# sense_part.net
KiCad netlist of a schematic drawn in EAGLE
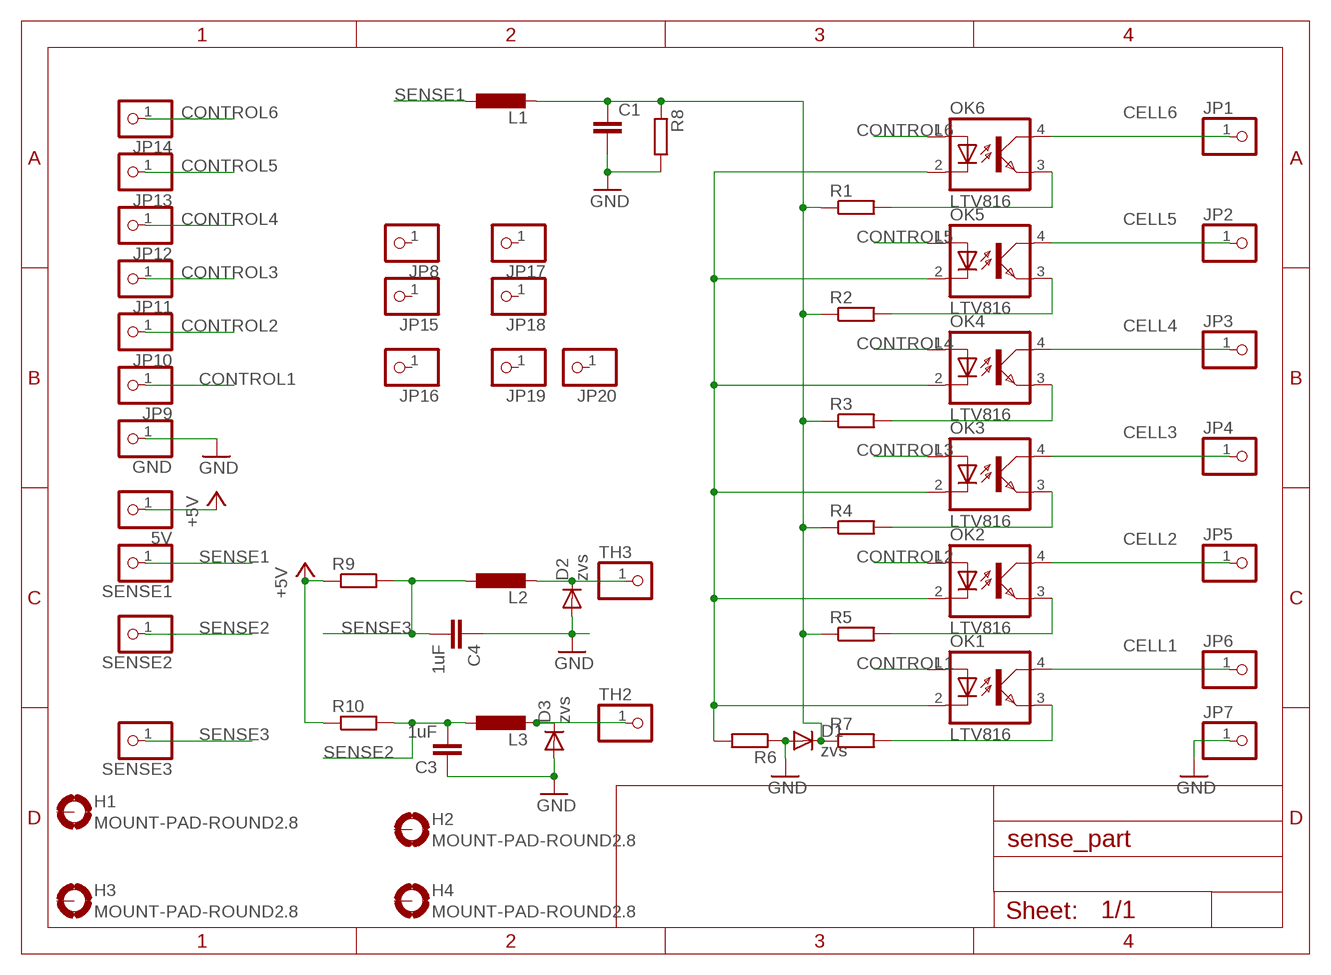
[diagram p0: schematic, sheet 1]

(export (version "E")
  (design (tool "Eeschema 10.0.6"))
  (components
    (comp (ref "5V")
      (value "PINHD-1X1")
      (footprint "eagle-import:1X01")
      (libsource (lib "eagle-import") (part "PINHD-1X1"))
    )
    (comp (ref "C1")
      (value "C-EU050-030X075")
      (footprint "eagle-import:C050-030X075")
      (libsource (lib "eagle-import") (part "C-EU050-030X075"))
    )
    (comp (ref "C3")
      (value "1uF")
      (footprint "eagle-import:C025-024X044")
      (libsource (lib "eagle-import") (part "resistor_C-EU025-024X044"))
    )
    (comp (ref "C4")
      (value "1uF")
      (footprint "eagle-import:C025-024X044")
      (libsource (lib "eagle-import") (part "resistor_C-EU025-024X044"))
    )
    (comp (ref "D1")
      (value "zvs")
      (footprint "eagle-import:SOD-123_MINI-SMA")
      (libsource (lib "eagle-import") (part "CGRM400-G1"))
    )
    (comp (ref "D2")
      (value "zvs")
      (footprint "eagle-import:SOD-123_MINI-SMA")
      (libsource (lib "eagle-import") (part "CGRM400-G1"))
    )
    (comp (ref "D3")
      (value "zvs")
      (footprint "eagle-import:SOD-123_MINI-SMA")
      (libsource (lib "eagle-import") (part "CGRM400-G1"))
    )
    (comp (ref "GND")
      (value "PINHD-1X1")
      (footprint "eagle-import:1X01")
      (libsource (lib "eagle-import") (part "PINHD-1X1"))
    )
    (comp (ref "H1")
      (value "MOUNT-PAD-ROUND2.8")
      (footprint "eagle-import:2,8-PAD")
      (libsource (lib "eagle-import") (part "MOUNT-PAD-ROUND2.8"))
    )
    (comp (ref "H2")
      (value "MOUNT-PAD-ROUND2.8")
      (footprint "eagle-import:2,8-PAD")
      (libsource (lib "eagle-import") (part "MOUNT-PAD-ROUND2.8"))
    )
    (comp (ref "H3")
      (value "MOUNT-PAD-ROUND2.8")
      (footprint "eagle-import:2,8-PAD")
      (libsource (lib "eagle-import") (part "MOUNT-PAD-ROUND2.8"))
    )
    (comp (ref "H4")
      (value "MOUNT-PAD-ROUND2.8")
      (footprint "eagle-import:2,8-PAD")
      (libsource (lib "eagle-import") (part "MOUNT-PAD-ROUND2.8"))
    )
    (comp (ref "JP1")
      (value "PINHD-1X1")
      (footprint "eagle-import:1X01")
      (libsource (lib "eagle-import") (part "PINHD-1X1"))
    )
    (comp (ref "JP2")
      (value "PINHD-1X1")
      (footprint "eagle-import:1X01")
      (libsource (lib "eagle-import") (part "PINHD-1X1"))
    )
    (comp (ref "JP3")
      (value "PINHD-1X1")
      (footprint "eagle-import:1X01")
      (libsource (lib "eagle-import") (part "PINHD-1X1"))
    )
    (comp (ref "JP4")
      (value "PINHD-1X1")
      (footprint "eagle-import:1X01")
      (libsource (lib "eagle-import") (part "PINHD-1X1"))
    )
    (comp (ref "JP5")
      (value "PINHD-1X1")
      (footprint "eagle-import:1X01")
      (libsource (lib "eagle-import") (part "PINHD-1X1"))
    )
    (comp (ref "JP6")
      (value "PINHD-1X1")
      (footprint "eagle-import:1X01")
      (libsource (lib "eagle-import") (part "PINHD-1X1"))
    )
    (comp (ref "JP7")
      (value "PINHD-1X1")
      (footprint "eagle-import:1X01")
      (libsource (lib "eagle-import") (part "PINHD-1X1"))
    )
    (comp (ref "JP8")
      (value "PINHD-1X1")
      (footprint "eagle-import:1X01")
      (libsource (lib "eagle-import") (part "PINHD-1X1"))
    )
    (comp (ref "JP9")
      (value "PINHD-1X1")
      (footprint "eagle-import:1X01")
      (libsource (lib "eagle-import") (part "PINHD-1X1"))
    )
    (comp (ref "JP10")
      (value "PINHD-1X1")
      (footprint "eagle-import:1X01")
      (libsource (lib "eagle-import") (part "PINHD-1X1"))
    )
    (comp (ref "JP11")
      (value "PINHD-1X1")
      (footprint "eagle-import:1X01")
      (libsource (lib "eagle-import") (part "PINHD-1X1"))
    )
    (comp (ref "JP12")
      (value "PINHD-1X1")
      (footprint "eagle-import:1X01")
      (libsource (lib "eagle-import") (part "PINHD-1X1"))
    )
    (comp (ref "JP13")
      (value "PINHD-1X1")
      (footprint "eagle-import:1X01")
      (libsource (lib "eagle-import") (part "PINHD-1X1"))
    )
    (comp (ref "JP14")
      (value "PINHD-1X1")
      (footprint "eagle-import:1X01")
      (libsource (lib "eagle-import") (part "PINHD-1X1"))
    )
    (comp (ref "JP15")
      (value "PINHD-1X1")
      (footprint "eagle-import:1X01")
      (libsource (lib "eagle-import") (part "PINHD-1X1"))
    )
    (comp (ref "JP16")
      (value "PINHD-1X1")
      (footprint "eagle-import:1X01")
      (libsource (lib "eagle-import") (part "PINHD-1X1"))
    )
    (comp (ref "JP17")
      (value "PINHD-1X1")
      (footprint "eagle-import:1X01")
      (libsource (lib "eagle-import") (part "PINHD-1X1"))
    )
    (comp (ref "JP18")
      (value "PINHD-1X1")
      (footprint "eagle-import:1X01")
      (libsource (lib "eagle-import") (part "PINHD-1X1"))
    )
    (comp (ref "JP19")
      (value "PINHD-1X1")
      (footprint "eagle-import:1X01")
      (libsource (lib "eagle-import") (part "PINHD-1X1"))
    )
    (comp (ref "JP20")
      (value "PINHD-1X1")
      (footprint "eagle-import:1X01")
      (libsource (lib "eagle-import") (part "PINHD-1X1"))
    )
    (comp (ref "L1")
      (value "L-EU0207/12")
      (footprint "eagle-import:0207_12")
      (libsource (lib "eagle-import") (part "L-EU0207/12"))
    )
    (comp (ref "L2")
      (value "L-EU0207/12")
      (footprint "eagle-import:0207_12")
      (libsource (lib "eagle-import") (part "L-EU0207/12"))
    )
    (comp (ref "L3")
      (value "L-EU0207/12")
      (footprint "eagle-import:0207_12")
      (libsource (lib "eagle-import") (part "L-EU0207/12"))
    )
    (comp (ref "OK1")
      (value "LTV816")
      (footprint "eagle-import:DIL04")
      (libsource (lib "eagle-import") (part "LTV816"))
    )
    (comp (ref "OK2")
      (value "LTV816")
      (footprint "eagle-import:DIL04")
      (libsource (lib "eagle-import") (part "LTV816"))
    )
    (comp (ref "OK3")
      (value "LTV816")
      (footprint "eagle-import:DIL04")
      (libsource (lib "eagle-import") (part "LTV816"))
    )
    (comp (ref "OK4")
      (value "LTV816")
      (footprint "eagle-import:DIL04")
      (libsource (lib "eagle-import") (part "LTV816"))
    )
    (comp (ref "OK5")
      (value "LTV816")
      (footprint "eagle-import:DIL04")
      (libsource (lib "eagle-import") (part "LTV816"))
    )
    (comp (ref "OK6")
      (value "LTV816")
      (footprint "eagle-import:DIL04")
      (libsource (lib "eagle-import") (part "LTV816"))
    )
    (comp (ref "R1")
      (value "R-EU_R1206")
      (footprint "eagle-import:R1206")
      (libsource (lib "eagle-import") (part "R-EU_R1206"))
    )
    (comp (ref "R2")
      (value "R-EU_R1206")
      (footprint "eagle-import:R1206")
      (libsource (lib "eagle-import") (part "R-EU_R1206"))
    )
    (comp (ref "R3")
      (value "R-EU_R1206")
      (footprint "eagle-import:R1206")
      (libsource (lib "eagle-import") (part "R-EU_R1206"))
    )
    (comp (ref "R4")
      (value "R-EU_R1206")
      (footprint "eagle-import:R1206")
      (libsource (lib "eagle-import") (part "R-EU_R1206"))
    )
    (comp (ref "R5")
      (value "R-EU_R1206")
      (footprint "eagle-import:R1206")
      (libsource (lib "eagle-import") (part "R-EU_R1206"))
    )
    (comp (ref "R6")
      (value "R-EU_R1206")
      (footprint "eagle-import:R1206")
      (libsource (lib "eagle-import") (part "R-EU_R1206"))
    )
    (comp (ref "R7")
      (value "R-EU_R1206")
      (footprint "eagle-import:R1206")
      (libsource (lib "eagle-import") (part "R-EU_R1206"))
    )
    (comp (ref "R8")
      (value "R-EU_R1206")
      (footprint "eagle-import:R1206")
      (libsource (lib "eagle-import") (part "R-EU_R1206"))
    )
    (comp (ref "R9")
      (value "R-EU_R1206")
      (footprint "eagle-import:R1206")
      (libsource (lib "eagle-import") (part "R-EU_R1206"))
    )
    (comp (ref "R10")
      (value "R-EU_R1206")
      (footprint "eagle-import:R1206")
      (libsource (lib "eagle-import") (part "R-EU_R1206"))
    )
    (comp (ref "SENSE1")
      (value "PINHD-1X1")
      (footprint "eagle-import:1X01")
      (libsource (lib "eagle-import") (part "PINHD-1X1"))
    )
    (comp (ref "SENSE2")
      (value "PINHD-1X1")
      (footprint "eagle-import:1X01")
      (libsource (lib "eagle-import") (part "PINHD-1X1"))
    )
    (comp (ref "SENSE3")
      (value "PINHD-1X1")
      (footprint "eagle-import:1X01")
      (libsource (lib "eagle-import") (part "PINHD-1X1"))
    )
    (comp (ref "TH2")
      (value "PINHD-1X1")
      (footprint "eagle-import:1X01")
      (libsource (lib "eagle-import") (part "PINHD-1X1"))
    )
    (comp (ref "TH3")
      (value "PINHD-1X1")
      (footprint "eagle-import:1X01")
      (libsource (lib "eagle-import") (part "PINHD-1X1"))
    )
  )
  (nets
    (net (code "1") (name "+5V") (class "Default")
      (node (ref "5V") (pin "1") (pinfunction "1_1") (pintype "passive"))
      (node (ref "R10") (pin "1") (pinfunction "1_1") (pintype "passive"))
      (node (ref "R9") (pin "1") (pinfunction "1_1") (pintype "passive"))
    )
    (net (code "2") (name "/CELL1") (class "Default")
      (node (ref "JP6") (pin "1") (pinfunction "1_1") (pintype "passive"))
      (node (ref "OK1") (pin "4") (pinfunction "COL_4") (pintype "passive"))
    )
    (net (code "3") (name "/CELL2") (class "Default")
      (node (ref "JP5") (pin "1") (pinfunction "1_1") (pintype "passive"))
      (node (ref "OK2") (pin "4") (pinfunction "COL_4") (pintype "passive"))
    )
    (net (code "4") (name "/CELL3") (class "Default")
      (node (ref "JP4") (pin "1") (pinfunction "1_1") (pintype "passive"))
      (node (ref "OK3") (pin "4") (pinfunction "COL_4") (pintype "passive"))
    )
    (net (code "5") (name "/CELL4") (class "Default")
      (node (ref "JP3") (pin "1") (pinfunction "1_1") (pintype "passive"))
      (node (ref "OK4") (pin "4") (pinfunction "COL_4") (pintype "passive"))
    )
    (net (code "6") (name "/CELL5") (class "Default")
      (node (ref "JP2") (pin "1") (pinfunction "1_1") (pintype "passive"))
      (node (ref "OK5") (pin "4") (pinfunction "COL_4") (pintype "passive"))
    )
    (net (code "7") (name "/CELL6") (class "Default")
      (node (ref "JP1") (pin "1") (pinfunction "1_1") (pintype "passive"))
      (node (ref "OK6") (pin "4") (pinfunction "COL_4") (pintype "passive"))
    )
    (net (code "8") (name "/CONTROL1") (class "Default")
      (node (ref "JP9") (pin "1") (pinfunction "1_1") (pintype "passive"))
      (node (ref "OK1") (pin "1") (pinfunction "A_1") (pintype "passive"))
    )
    (net (code "9") (name "/CONTROL2") (class "Default")
      (node (ref "JP10") (pin "1") (pinfunction "1_1") (pintype "passive"))
      (node (ref "OK2") (pin "1") (pinfunction "A_1") (pintype "passive"))
    )
    (net (code "10") (name "/CONTROL3") (class "Default")
      (node (ref "JP11") (pin "1") (pinfunction "1_1") (pintype "passive"))
      (node (ref "OK3") (pin "1") (pinfunction "A_1") (pintype "passive"))
    )
    (net (code "11") (name "/CONTROL4") (class "Default")
      (node (ref "JP12") (pin "1") (pinfunction "1_1") (pintype "passive"))
      (node (ref "OK4") (pin "1") (pinfunction "A_1") (pintype "passive"))
    )
    (net (code "12") (name "/CONTROL5") (class "Default")
      (node (ref "JP13") (pin "1") (pinfunction "1_1") (pintype "passive"))
      (node (ref "OK5") (pin "1") (pinfunction "A_1") (pintype "passive"))
    )
    (net (code "13") (name "/CONTROL6") (class "Default")
      (node (ref "JP14") (pin "1") (pinfunction "1_1") (pintype "passive"))
      (node (ref "OK6") (pin "1") (pinfunction "A_1") (pintype "passive"))
    )
    (net (code "14") (name "/SENSE1") (class "Default")
      (node (ref "L1") (pin "1") (pinfunction "1_1") (pintype "passive"))
      (node (ref "SENSE1") (pin "1") (pinfunction "1_1") (pintype "passive"))
    )
    (net (code "15") (name "/SENSE2") (class "Default")
      (node (ref "C3") (pin "2") (pinfunction "2_2") (pintype "passive"))
      (node (ref "L3") (pin "1") (pinfunction "1_1") (pintype "passive"))
      (node (ref "R10") (pin "2") (pinfunction "2_2") (pintype "passive"))
      (node (ref "SENSE2") (pin "1") (pinfunction "1_1") (pintype "passive"))
    )
    (net (code "16") (name "/SENSE3") (class "Default")
      (node (ref "C4") (pin "2") (pinfunction "2_2") (pintype "passive"))
      (node (ref "L2") (pin "1") (pinfunction "1_1") (pintype "passive"))
      (node (ref "R9") (pin "2") (pinfunction "2_2") (pintype "passive"))
      (node (ref "SENSE3") (pin "1") (pinfunction "1_1") (pintype "passive"))
    )
    (net (code "17") (name "GND") (class "Default")
      (node (ref "C1") (pin "2") (pinfunction "2_2") (pintype "passive"))
      (node (ref "C3") (pin "1") (pinfunction "1_1") (pintype "passive"))
      (node (ref "C4") (pin "1") (pinfunction "1_1") (pintype "passive"))
      (node (ref "D1") (pin "A") (pinfunction "A_A") (pintype "passive"))
      (node (ref "D2") (pin "A") (pinfunction "A_A") (pintype "passive"))
      (node (ref "D3") (pin "A") (pinfunction "A_A") (pintype "passive"))
      (node (ref "GND") (pin "1") (pinfunction "1_1") (pintype "passive"))
      (node (ref "JP7") (pin "1") (pinfunction "1_1") (pintype "passive"))
      (node (ref "R6") (pin "1") (pinfunction "1_1") (pintype "passive"))
      (node (ref "R8") (pin "2") (pinfunction "2_2") (pintype "passive"))
    )
    (net (code "18") (name "Net-(C1-Pad1)") (class "Default")
      (node (ref "C1") (pin "1") (pinfunction "1_1") (pintype "passive"))
      (node (ref "D1") (pin "C") (pinfunction "C_C") (pintype "passive"))
      (node (ref "L1") (pin "2") (pinfunction "2_2") (pintype "passive"))
      (node (ref "R1") (pin "1") (pinfunction "1_1") (pintype "passive"))
      (node (ref "R2") (pin "1") (pinfunction "1_1") (pintype "passive"))
      (node (ref "R3") (pin "1") (pinfunction "1_1") (pintype "passive"))
      (node (ref "R4") (pin "1") (pinfunction "1_1") (pintype "passive"))
      (node (ref "R5") (pin "1") (pinfunction "1_1") (pintype "passive"))
      (node (ref "R7") (pin "1") (pinfunction "1_1") (pintype "passive"))
      (node (ref "R8") (pin "1") (pinfunction "1_1") (pintype "passive"))
    )
    (net (code "19") (name "Net-(D2-PadC)") (class "Default")
      (node (ref "D2") (pin "C") (pinfunction "C_C") (pintype "passive"))
      (node (ref "L2") (pin "2") (pinfunction "2_2") (pintype "passive"))
      (node (ref "TH3") (pin "1") (pinfunction "1_1") (pintype "passive"))
    )
    (net (code "20") (name "Net-(D3-PadC)") (class "Default")
      (node (ref "D3") (pin "C") (pinfunction "C_C") (pintype "passive"))
      (node (ref "L3") (pin "2") (pinfunction "2_2") (pintype "passive"))
      (node (ref "TH2") (pin "1") (pinfunction "1_1") (pintype "passive"))
    )
    (net (code "21") (name "Net-(OK1-C)") (class "Default")
      (node (ref "OK1") (pin "2") (pinfunction "C_2") (pintype "passive"))
      (node (ref "OK2") (pin "2") (pinfunction "C_2") (pintype "passive"))
      (node (ref "OK3") (pin "2") (pinfunction "C_2") (pintype "passive"))
      (node (ref "OK4") (pin "2") (pinfunction "C_2") (pintype "passive"))
      (node (ref "OK5") (pin "2") (pinfunction "C_2") (pintype "passive"))
      (node (ref "OK6") (pin "2") (pinfunction "C_2") (pintype "passive"))
      (node (ref "R6") (pin "2") (pinfunction "2_2") (pintype "passive"))
    )
    (net (code "22") (name "Net-(OK1-EMIT)") (class "Default")
      (node (ref "OK1") (pin "3") (pinfunction "EMIT_3") (pintype "passive"))
      (node (ref "R7") (pin "2") (pinfunction "2_2") (pintype "passive"))
    )
    (net (code "23") (name "Net-(OK2-EMIT)") (class "Default")
      (node (ref "OK2") (pin "3") (pinfunction "EMIT_3") (pintype "passive"))
      (node (ref "R5") (pin "2") (pinfunction "2_2") (pintype "passive"))
    )
    (net (code "24") (name "Net-(OK3-EMIT)") (class "Default")
      (node (ref "OK3") (pin "3") (pinfunction "EMIT_3") (pintype "passive"))
      (node (ref "R4") (pin "2") (pinfunction "2_2") (pintype "passive"))
    )
    (net (code "25") (name "Net-(OK4-EMIT)") (class "Default")
      (node (ref "OK4") (pin "3") (pinfunction "EMIT_3") (pintype "passive"))
      (node (ref "R3") (pin "2") (pinfunction "2_2") (pintype "passive"))
    )
    (net (code "26") (name "Net-(OK5-EMIT)") (class "Default")
      (node (ref "OK5") (pin "3") (pinfunction "EMIT_3") (pintype "passive"))
      (node (ref "R2") (pin "2") (pinfunction "2_2") (pintype "passive"))
    )
    (net (code "27") (name "Net-(OK6-EMIT)") (class "Default")
      (node (ref "OK6") (pin "3") (pinfunction "EMIT_3") (pintype "passive"))
      (node (ref "R1") (pin "2") (pinfunction "2_2") (pintype "passive"))
    )
    (net (code "28") (name "unconnected-(H1-MOUNT-PadB2,8)") (class "Default")
      (node (ref "H1") (pin "B2,8") (pinfunction "MOUNT_B2,8") (pintype "passive"))
    )
    (net (code "29") (name "unconnected-(H2-MOUNT-PadB2,8)") (class "Default")
      (node (ref "H2") (pin "B2,8") (pinfunction "MOUNT_B2,8") (pintype "passive"))
    )
    (net (code "30") (name "unconnected-(H3-MOUNT-PadB2,8)") (class "Default")
      (node (ref "H3") (pin "B2,8") (pinfunction "MOUNT_B2,8") (pintype "passive"))
    )
    (net (code "31") (name "unconnected-(H4-MOUNT-PadB2,8)") (class "Default")
      (node (ref "H4") (pin "B2,8") (pinfunction "MOUNT_B2,8") (pintype "passive"))
    )
    (net (code "32") (name "unconnected-(JP8-Pad1)") (class "Default")
      (node (ref "JP8") (pin "1") (pinfunction "1_1") (pintype "passive"))
    )
    (net (code "33") (name "unconnected-(JP15-Pad1)") (class "Default")
      (node (ref "JP15") (pin "1") (pinfunction "1_1") (pintype "passive"))
    )
    (net (code "34") (name "unconnected-(JP16-Pad1)") (class "Default")
      (node (ref "JP16") (pin "1") (pinfunction "1_1") (pintype "passive"))
    )
    (net (code "35") (name "unconnected-(JP17-Pad1)") (class "Default")
      (node (ref "JP17") (pin "1") (pinfunction "1_1") (pintype "passive"))
    )
    (net (code "36") (name "unconnected-(JP18-Pad1)") (class "Default")
      (node (ref "JP18") (pin "1") (pinfunction "1_1") (pintype "passive"))
    )
    (net (code "37") (name "unconnected-(JP19-Pad1)") (class "Default")
      (node (ref "JP19") (pin "1") (pinfunction "1_1") (pintype "passive"))
    )
    (net (code "38") (name "unconnected-(JP20-Pad1)") (class "Default")
      (node (ref "JP20") (pin "1") (pinfunction "1_1") (pintype "passive"))
    )
  )
)
